# Board.net
KiCad netlist of a schematic drawn in EAGLE
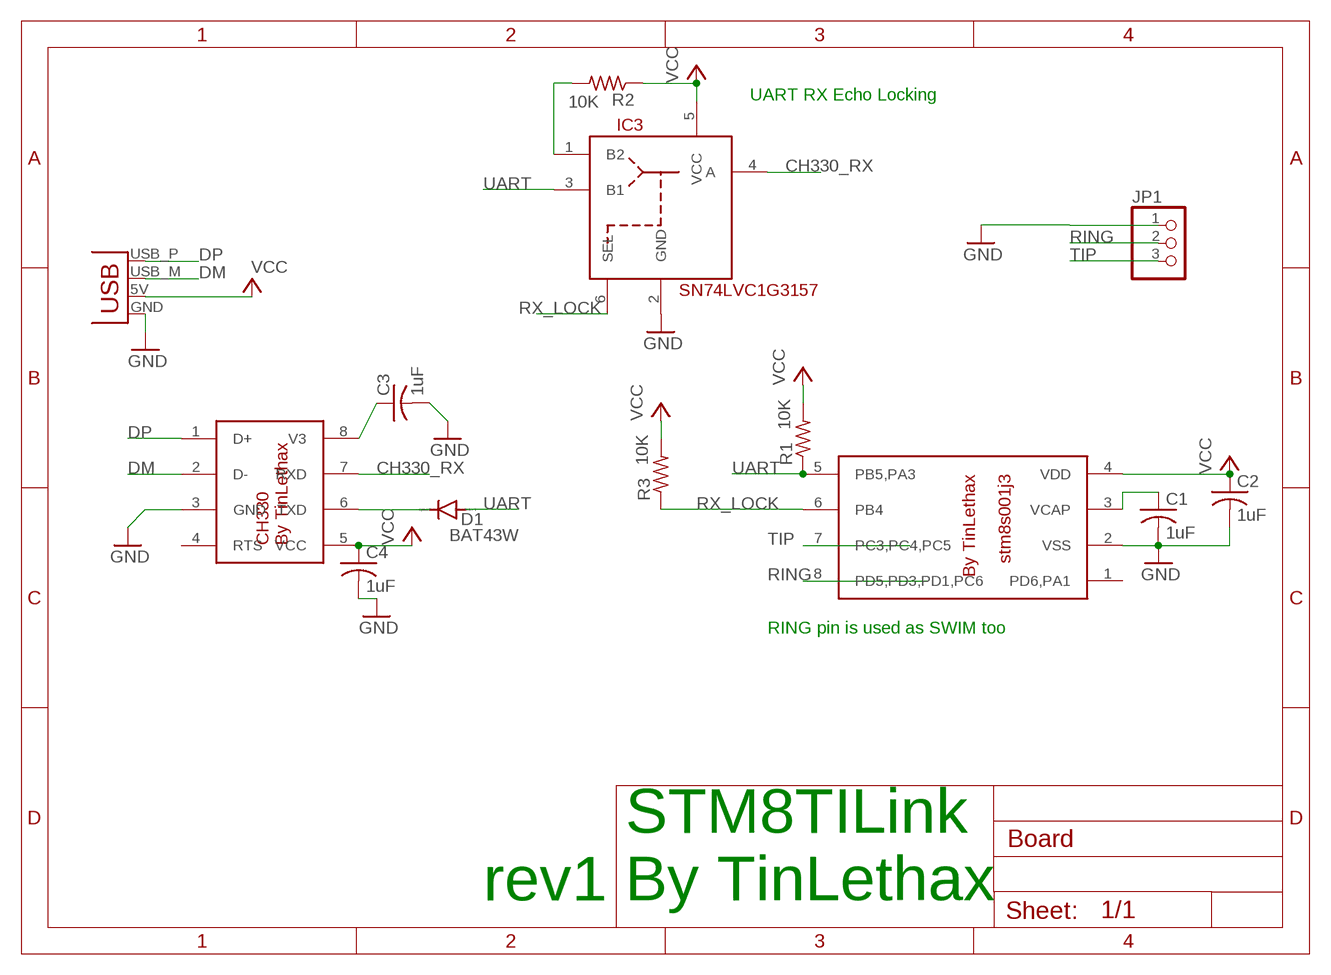
[diagram p0: schematic, sheet 1]

(export (version "E")
  (design (tool "Eeschema 10.0.6"))
  (components
    (comp (ref "C1")
      (value "1uF")
      (footprint "eagle-import:C0603")
      (libsource (lib "eagle-import") (part "C-USC0603"))
    )
    (comp (ref "C2")
      (value "1uF")
      (footprint "eagle-import:C0603")
      (libsource (lib "eagle-import") (part "C-USC0603"))
    )
    (comp (ref "C3")
      (value "1uF")
      (footprint "eagle-import:C0603")
      (libsource (lib "eagle-import") (part "C-USC0603"))
    )
    (comp (ref "C4")
      (value "1uF")
      (footprint "eagle-import:C0603")
      (libsource (lib "eagle-import") (part "C-USC0603"))
    )
    (comp (ref "D1")
      (value "BAT43W")
      (footprint "eagle-import:SOD-123_MINI-SMA")
      (libsource (lib "eagle-import") (part "CGRM400-G"))
    )
    (comp (ref "IC1")
      (value "STM8S001J3")
      (footprint "eagle-import:SOP8")
      (libsource (lib "eagle-import") (part "STM8S001J3"))
    )
    (comp (ref "IC2")
      (value "CH330")
      (footprint "eagle-import:SOIC127P600X150-8N")
      (libsource (lib "eagle-import") (part "CH330"))
    )
    (comp (ref "IC3")
      (value "SN74LVC1G3157")
      (footprint "eagle-import:SOT95P280X145-6N")
      (libsource (lib "eagle-import") (part "SN74LVC1G3157"))
    )
    (comp (ref "JP1")
      (value "PINHD-1X3")
      (footprint "eagle-import:1X03")
      (libsource (lib "eagle-import") (part "PINHD-1X3"))
    )
    (comp (ref "R1")
      (value "10K")
      (footprint "eagle-import:R0603")
      (libsource (lib "eagle-import") (part "R-US_R0603"))
    )
    (comp (ref "R2")
      (value "10K")
      (footprint "eagle-import:R0603")
      (libsource (lib "eagle-import") (part "R-US_R0603"))
    )
    (comp (ref "R3")
      (value "10K")
      (footprint "eagle-import:R0603")
      (libsource (lib "eagle-import") (part "R-US_R0603"))
    )
    (comp (ref "X1")
      (value "USB_USBPCB")
      (footprint "eagle-import:USB_USB-A-PCB")
      (libsource (lib "eagle-import") (part "USB_USBPCB"))
    )
  )
  (nets
    (net (code "1") (name "/CH330_RX") (class "Default")
      (node (ref "IC2") (pin "7") (pinfunction "RXD_7") (pintype "bidirectional"))
      (node (ref "IC3") (pin "4") (pinfunction "A_4") (pintype "bidirectional"))
    )
    (net (code "2") (name "/DM") (class "Default")
      (node (ref "IC2") (pin "2") (pinfunction "D-_2") (pintype "bidirectional"))
      (node (ref "X1") (pin "USB_M") (pinfunction "D-_USB_M") (pintype "bidirectional"))
    )
    (net (code "3") (name "/DP") (class "Default")
      (node (ref "IC2") (pin "1") (pinfunction "D+_1") (pintype "bidirectional"))
      (node (ref "X1") (pin "USB_P") (pinfunction "D+_USB_P") (pintype "bidirectional"))
    )
    (net (code "4") (name "/RING") (class "Default")
      (node (ref "IC1") (pin "8") (pinfunction "PD5,PD3,PD1,PC6_8") (pintype "bidirectional"))
      (node (ref "JP1") (pin "2") (pinfunction "2_2") (pintype "passive"))
    )
    (net (code "5") (name "/RX_LOCK") (class "Default")
      (node (ref "IC1") (pin "6") (pinfunction "PB4_6") (pintype "bidirectional"))
      (node (ref "IC3") (pin "6") (pinfunction "SEL_6") (pintype "bidirectional"))
      (node (ref "R3") (pin "1") (pinfunction "1_1") (pintype "passive"))
    )
    (net (code "6") (name "/TIP") (class "Default")
      (node (ref "IC1") (pin "7") (pinfunction "PC3,PC4,PC5_7") (pintype "bidirectional"))
      (node (ref "JP1") (pin "3") (pinfunction "3_3") (pintype "passive"))
    )
    (net (code "7") (name "/UART") (class "Default")
      (node (ref "D1") (pin "A") (pinfunction "A_A") (pintype "passive"))
      (node (ref "IC1") (pin "5") (pinfunction "PB5,PA3_5") (pintype "bidirectional"))
      (node (ref "IC3") (pin "3") (pinfunction "B1_3") (pintype "bidirectional"))
      (node (ref "R1") (pin "1") (pinfunction "1_1") (pintype "passive"))
    )
    (net (code "8") (name "GND") (class "Default")
      (node (ref "C1") (pin "2") (pinfunction "2_2") (pintype "passive"))
      (node (ref "C2") (pin "2") (pinfunction "2_2") (pintype "passive"))
      (node (ref "C3") (pin "2") (pinfunction "2_2") (pintype "passive"))
      (node (ref "C4") (pin "2") (pinfunction "2_2") (pintype "passive"))
      (node (ref "IC1") (pin "2") (pinfunction "VSS_2") (pintype "bidirectional"))
      (node (ref "IC2") (pin "3") (pinfunction "GND_3") (pintype "bidirectional"))
      (node (ref "IC3") (pin "2") (pinfunction "GND_2") (pintype "bidirectional"))
      (node (ref "JP1") (pin "1") (pinfunction "1_1") (pintype "passive"))
      (node (ref "X1") (pin "GND") (pinfunction "GND_GND") (pintype "bidirectional"))
    )
    (net (code "9") (name "Net-(IC1-VCAP)") (class "Default")
      (node (ref "C1") (pin "1") (pinfunction "1_1") (pintype "passive"))
      (node (ref "IC1") (pin "3") (pinfunction "VCAP_3") (pintype "bidirectional"))
    )
    (net (code "10") (name "Net-(IC2-TXD)") (class "Default")
      (node (ref "D1") (pin "C") (pinfunction "C_C") (pintype "passive"))
      (node (ref "IC2") (pin "6") (pinfunction "TXD_6") (pintype "bidirectional"))
    )
    (net (code "11") (name "Net-(IC2-V3)") (class "Default")
      (node (ref "C3") (pin "1") (pinfunction "1_1") (pintype "passive"))
      (node (ref "IC2") (pin "8") (pinfunction "V3_8") (pintype "bidirectional"))
    )
    (net (code "12") (name "Net-(IC3-B2)") (class "Default")
      (node (ref "IC3") (pin "1") (pinfunction "B2_1") (pintype "bidirectional"))
      (node (ref "R2") (pin "2") (pinfunction "2_2") (pintype "passive"))
    )
    (net (code "13") (name "VCC") (class "Default")
      (node (ref "C2") (pin "1") (pinfunction "1_1") (pintype "passive"))
      (node (ref "C4") (pin "1") (pinfunction "1_1") (pintype "passive"))
      (node (ref "IC1") (pin "4") (pinfunction "VDD_4") (pintype "bidirectional"))
      (node (ref "IC2") (pin "5") (pinfunction "VCC_5") (pintype "bidirectional"))
      (node (ref "IC3") (pin "5") (pinfunction "VCC_5") (pintype "bidirectional"))
      (node (ref "R1") (pin "2") (pinfunction "2_2") (pintype "passive"))
      (node (ref "R2") (pin "1") (pinfunction "1_1") (pintype "passive"))
      (node (ref "R3") (pin "2") (pinfunction "2_2") (pintype "passive"))
      (node (ref "X1") (pin "5V") (pinfunction "VBUS_5V") (pintype "bidirectional"))
    )
    (net (code "14") (name "unconnected-(IC1-PD6,PA1-Pad1)") (class "Default")
      (node (ref "IC1") (pin "1") (pinfunction "PD6,PA1_1") (pintype "bidirectional"))
    )
    (net (code "15") (name "unconnected-(IC2-RTS-Pad4)") (class "Default")
      (node (ref "IC2") (pin "4") (pinfunction "RTS_4") (pintype "bidirectional"))
    )
  )
)
